# io_a.net
KiCad netlist of a schematic drawn in Altium Designer
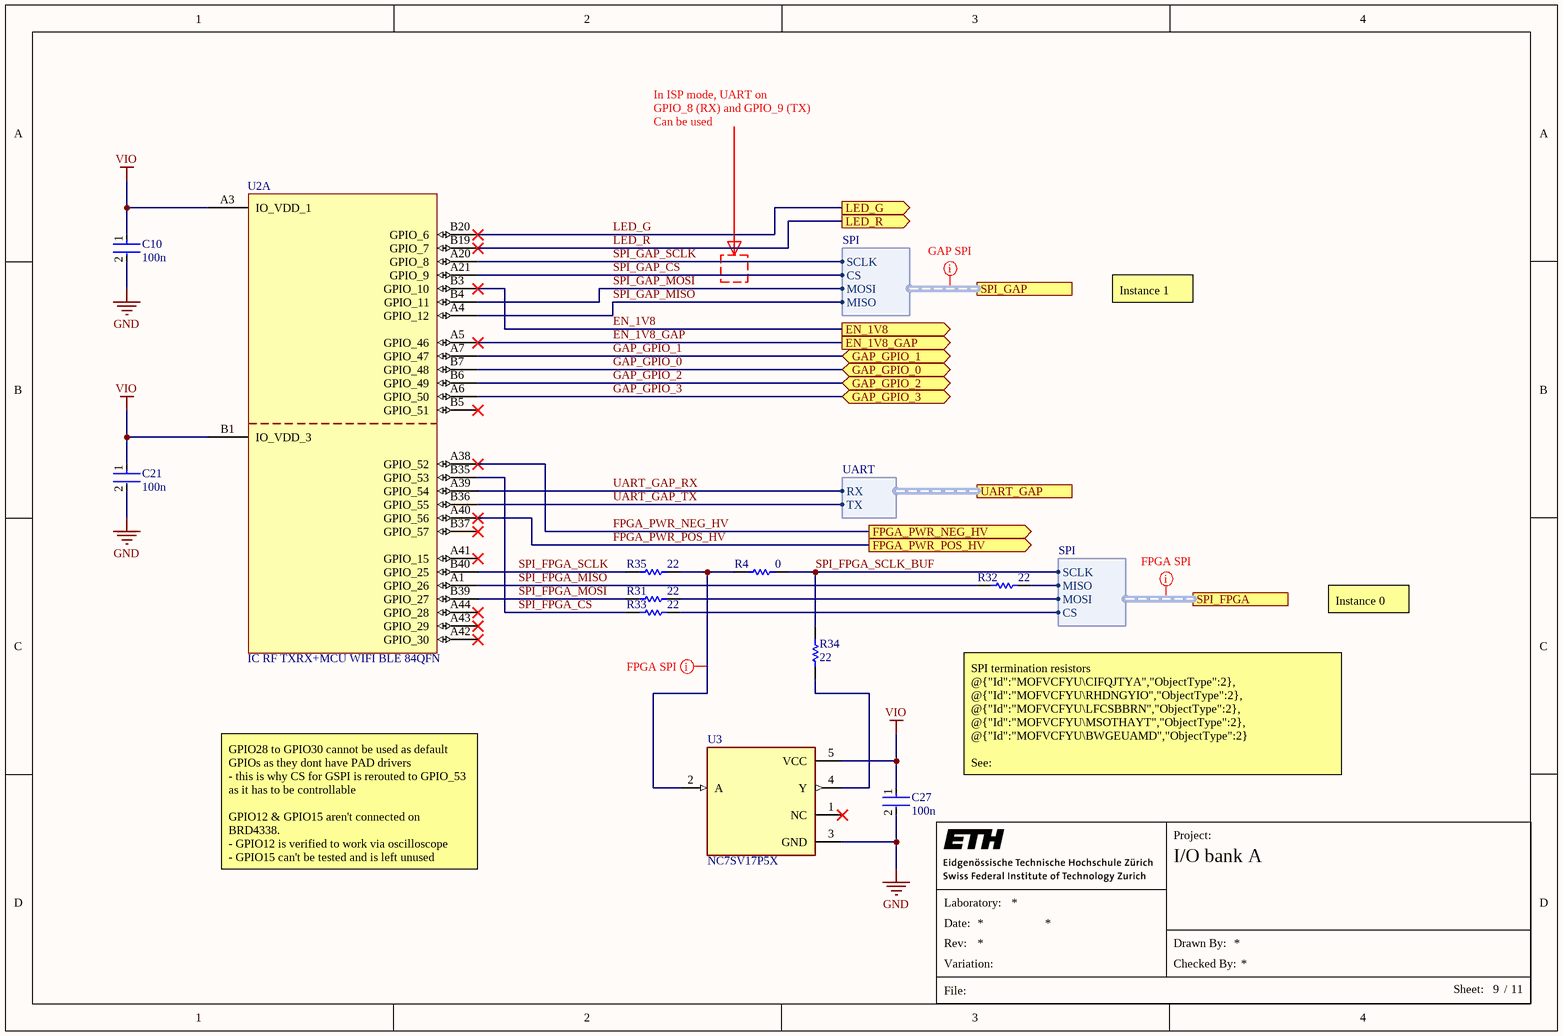
[diagram p0: io_a.SchDoc]

(export (version "E")
  (design (tool "Eeschema 10.0.6"))
  (components
    (comp (ref "C10")
      (value "100n")
      (footprint "FP-GRT155-0_05-MFG")
      (description "Multi-Layer Ceramic Capacitor 100nF 50V X7R ±10% 0402 Paper T/R")
      (libsource (lib "Altium Content Vault") (part "02cd4be3c70576c341d710602a673aa"))
    )
    (comp (ref "C21")
      (value "100n")
      (footprint "FP-GRT155-0_05-MFG")
      (description "Multi-Layer Ceramic Capacitor 100nF 50V X7R ±10% 0402 Paper T/R")
      (libsource (lib "Altium Content Vault") (part "02cd4be3c70576c341d710602a673aa"))
    )
    (comp (ref "C27")
      (value "100n")
      (footprint "FP-GRT155-0_05-MFG")
      (description "Multi-Layer Ceramic Capacitor 100nF 50V X7R ±10% 0402 Paper T/R")
      (libsource (lib "Altium Content Vault") (part "02cd4be3c70576c341d710602a673aa"))
    )
    (comp (ref "R4")
      (value "0")
      (footprint "RESC1005X40X25ML05T10")
      (description "Chip Resistor, 0 Ohm, 0.063 W, -55 to 155 degC, 0402 (1005 Metric)")
      (fields (field (name "POWER") "63mW") (field (name "Comment") "Resistor 0R 0402 63 mW"))
      (libsource (lib "Cédric's Workspace") (part "RES-2"))
    )
    (comp (ref "R31")
      (value "22")
      (footprint "RESC1005X40X25LL05T10")
      (fields (field (name "MANUFACTURER") "Yageo / Phycomp") (field (name "PART NUMBER") "RC0402FR-0722RL"))
      (libsource (lib "Altium Content Vault") (part "RES"))
    )
    (comp (ref "R32")
      (value "22")
      (footprint "RESC1005X40X25LL05T10")
      (fields (field (name "MANUFACTURER") "Yageo / Phycomp") (field (name "PART NUMBER") "RC0402FR-0722RL"))
      (libsource (lib "Altium Content Vault") (part "RES"))
    )
    (comp (ref "R33")
      (value "22")
      (footprint "RESC1005X40X25LL05T10")
      (fields (field (name "MANUFACTURER") "Yageo / Phycomp") (field (name "PART NUMBER") "RC0402FR-0722RL"))
      (libsource (lib "Altium Content Vault") (part "RES"))
    )
    (comp (ref "R34")
      (value "22")
      (footprint "RESC1005X40X25LL05T10")
      (fields (field (name "MANUFACTURER") "Yageo / Phycomp") (field (name "PART NUMBER") "RC0402FR-0722RL"))
      (libsource (lib "Altium Content Vault") (part "RES"))
    )
    (comp (ref "R35")
      (value "22")
      (footprint "RESC1005X40X25LL05T10")
      (fields (field (name "MANUFACTURER") "Yageo / Phycomp") (field (name "PART NUMBER") "RC0402FR-0722RL"))
      (libsource (lib "Altium Content Vault") (part "RES"))
    )
    (comp (ref "U2")
      (value "IC RF TXRX+MCU WIFI BLE 84QFN")
      (footprint "SIWG917M110LGTBA")
      (libsource (lib "SiWG917") (part "SIWG917"))
    )
    (comp (ref "U3")
      (value "NC7SV17P5X")
      (footprint "NC7SV17P5X:SOT65P210X110-5N")
      (description "Buffer, Non-Inverting 1 Element 1 Bit per Element Push-Pull Output SC-70-5")
      (fields (field (name "MF") "{'manufacturer': u'ON Semiconductor'}"))
      (libsource (lib "*") (part "NC7SV17P5X"))
    )
  )
  (nets
    (net (code "3") (name "/EN_1V8") (class "Default")
      (node (ref "U2") (pin "B3") (pinfunction "GPIO_10_B3") (pintype "bidirectional+no_connect"))
    )
    (net (code "4") (name "/EN_1V8_GAP") (class "Default")
      (node (ref "U2") (pin "A5") (pinfunction "GPIO_46_A5") (pintype "bidirectional+no_connect"))
    )
    (net (code "5") (name "/FPGA_PWR_NEG_HV") (class "Default")
      (node (ref "U2") (pin "A38") (pinfunction "GPIO_52_A38") (pintype "bidirectional+no_connect"))
    )
    (net (code "6") (name "/FPGA_PWR_POS_HV") (class "Default")
      (node (ref "U2") (pin "A40") (pinfunction "GPIO_56_A40") (pintype "bidirectional+no_connect"))
    )
    (net (code "7") (name "/GAP_GPIO_0") (class "Default")
      (node (ref "U2") (pin "B7") (pinfunction "GPIO_48_B7") (pintype "bidirectional"))
    )
    (net (code "8") (name "/GAP_GPIO_1") (class "Default")
      (node (ref "U2") (pin "A7") (pinfunction "GPIO_47_A7") (pintype "bidirectional"))
    )
    (net (code "9") (name "/GAP_GPIO_2") (class "Default")
      (node (ref "U2") (pin "B6") (pinfunction "GPIO_49_B6") (pintype "bidirectional"))
    )
    (net (code "10") (name "/GAP_GPIO_3") (class "Default")
      (node (ref "U2") (pin "A6") (pinfunction "GPIO_50_A6") (pintype "bidirectional"))
    )
    (net (code "11") (name "/LED_G") (class "Default")
      (node (ref "U2") (pin "B20") (pinfunction "GPIO_6_B20") (pintype "bidirectional+no_connect"))
    )
    (net (code "12") (name "/LED_R") (class "Default")
      (node (ref "U2") (pin "B19") (pinfunction "GPIO_7_B19") (pintype "bidirectional+no_connect"))
    )
    (net (code "13") (name "/SPI_FPGA_CS") (class "Default")
      (node (ref "R33") (pin "1") (pinfunction "1_1") (pintype "passive"))
      (node (ref "U2") (pin "B35") (pinfunction "GPIO_53_B35") (pintype "bidirectional"))
    )
    (net (code "14") (name "/SPI_FPGA_MISO") (class "Default")
      (node (ref "R32") (pin "1") (pinfunction "1_1") (pintype "passive"))
      (node (ref "U2") (pin "A1") (pinfunction "GPIO_26_A1") (pintype "bidirectional"))
    )
    (net (code "15") (name "/SPI_FPGA_MOSI") (class "Default")
      (node (ref "R31") (pin "1") (pinfunction "1_1") (pintype "passive"))
      (node (ref "U2") (pin "B39") (pinfunction "GPIO_27_B39") (pintype "bidirectional"))
    )
    (net (code "16") (name "/SPI_FPGA_SCLK") (class "Default")
      (node (ref "R35") (pin "1") (pinfunction "1_1") (pintype "passive"))
      (node (ref "U2") (pin "B40") (pinfunction "GPIO_25_B40") (pintype "bidirectional"))
    )
    (net (code "17") (name "/SPI_FPGA_SCLK_BUF") (class "Default")
      (node (ref "R34") (pin "2") (pinfunction "2_2") (pintype "passive"))
      (node (ref "R4") (pin "2") (pinfunction "2_2") (pintype "passive"))
    )
    (net (code "18") (name "/SPI_GAP_CS") (class "Default")
      (node (ref "U2") (pin "A21") (pinfunction "GPIO_9_A21") (pintype "bidirectional"))
    )
    (net (code "19") (name "/SPI_GAP_MISO") (class "Default")
      (node (ref "U2") (pin "A4") (pinfunction "GPIO_12_A4") (pintype "bidirectional"))
    )
    (net (code "20") (name "/SPI_GAP_MOSI") (class "Default")
      (node (ref "U2") (pin "B4") (pinfunction "GPIO_11_B4") (pintype "bidirectional"))
    )
    (net (code "21") (name "/SPI_GAP_SCLK") (class "Default")
      (node (ref "U2") (pin "A20") (pinfunction "GPIO_8_A20") (pintype "bidirectional"))
    )
    (net (code "22") (name "/UART_GAP_RX") (class "Default")
      (node (ref "U2") (pin "A39") (pinfunction "GPIO_54_A39") (pintype "bidirectional"))
    )
    (net (code "23") (name "/UART_GAP_TX") (class "Default")
      (node (ref "U2") (pin "B36") (pinfunction "GPIO_55_B36") (pintype "bidirectional"))
    )
    (net (code "26") (name "GND") (class "Default")
      (node (ref "C10") (pin "2") (pinfunction "2_2") (pintype "passive"))
      (node (ref "C21") (pin "2") (pinfunction "2_2") (pintype "passive"))
      (node (ref "C27") (pin "2") (pinfunction "2_2") (pintype "passive"))
      (node (ref "U3") (pin "3") (pinfunction "GND_3") (pintype "power_in"))
    )
    (net (code "27") (name "Net-(U3-A)") (class "Default")
      (node (ref "R35") (pin "2") (pinfunction "2_2") (pintype "passive"))
      (node (ref "R4") (pin "1") (pinfunction "1_1") (pintype "passive"))
      (node (ref "U3") (pin "2") (pinfunction "A_2") (pintype "input"))
    )
    (net (code "28") (name "Net-(U3-Y)") (class "Default")
      (node (ref "R34") (pin "1") (pinfunction "1_1") (pintype "passive"))
      (node (ref "U3") (pin "4") (pinfunction "Y_4") (pintype "output"))
    )
    (net (code "29") (name "VIO") (class "Default")
      (node (ref "C10") (pin "1") (pinfunction "1_1") (pintype "passive"))
      (node (ref "C21") (pin "1") (pinfunction "1_1") (pintype "passive"))
      (node (ref "C27") (pin "1") (pinfunction "1_1") (pintype "passive"))
      (node (ref "U2") (pin "A3") (pinfunction "IO_VDD_1_A3") (pintype "power_in"))
      (node (ref "U2") (pin "B1") (pinfunction "IO_VDD_3_B1") (pintype "power_in"))
      (node (ref "U3") (pin "5") (pinfunction "VCC_5") (pintype "power_in"))
    )
    (net (code "30") (name "unconnected-(R31-Pad2)") (class "Default")
      (node (ref "R31") (pin "2") (pinfunction "2_2") (pintype "passive"))
    )
    (net (code "31") (name "unconnected-(R32-Pad2)") (class "Default")
      (node (ref "R32") (pin "2") (pinfunction "2_2") (pintype "passive"))
    )
    (net (code "32") (name "unconnected-(R33-Pad2)") (class "Default")
      (node (ref "R33") (pin "2") (pinfunction "2_2") (pintype "passive"))
    )
    (net (code "33") (name "unconnected-(U2A-GPIO_15-PadA41)") (class "Default")
      (node (ref "U2") (pin "A41") (pinfunction "GPIO_15_A41") (pintype "bidirectional+no_connect"))
    )
    (net (code "34") (name "unconnected-(U2A-GPIO_28-PadA44)") (class "Default")
      (node (ref "U2") (pin "A44") (pinfunction "GPIO_28_A44") (pintype "bidirectional+no_connect"))
    )
    (net (code "35") (name "unconnected-(U2A-GPIO_29-PadA43)") (class "Default")
      (node (ref "U2") (pin "A43") (pinfunction "GPIO_29_A43") (pintype "bidirectional+no_connect"))
    )
    (net (code "36") (name "unconnected-(U2A-GPIO_30-PadA42)") (class "Default")
      (node (ref "U2") (pin "A42") (pinfunction "GPIO_30_A42") (pintype "bidirectional+no_connect"))
    )
    (net (code "37") (name "unconnected-(U2A-GPIO_51-PadB5)") (class "Default")
      (node (ref "U2") (pin "B5") (pinfunction "GPIO_51_B5") (pintype "bidirectional+no_connect"))
    )
    (net (code "38") (name "unconnected-(U2A-GPIO_57-PadB37)") (class "Default")
      (node (ref "U2") (pin "B37") (pinfunction "GPIO_57_B37") (pintype "bidirectional+no_connect"))
    )
    (net (code "39") (name "unconnected-(U3-NC-Pad1)") (class "Default")
      (node (ref "U3") (pin "1") (pinfunction "NC_1") (pintype "passive+no_connect"))
    )
  )
)
